# Adafruit_NeoPixel_8_Stick.net
KiCad netlist of a schematic drawn in EAGLE
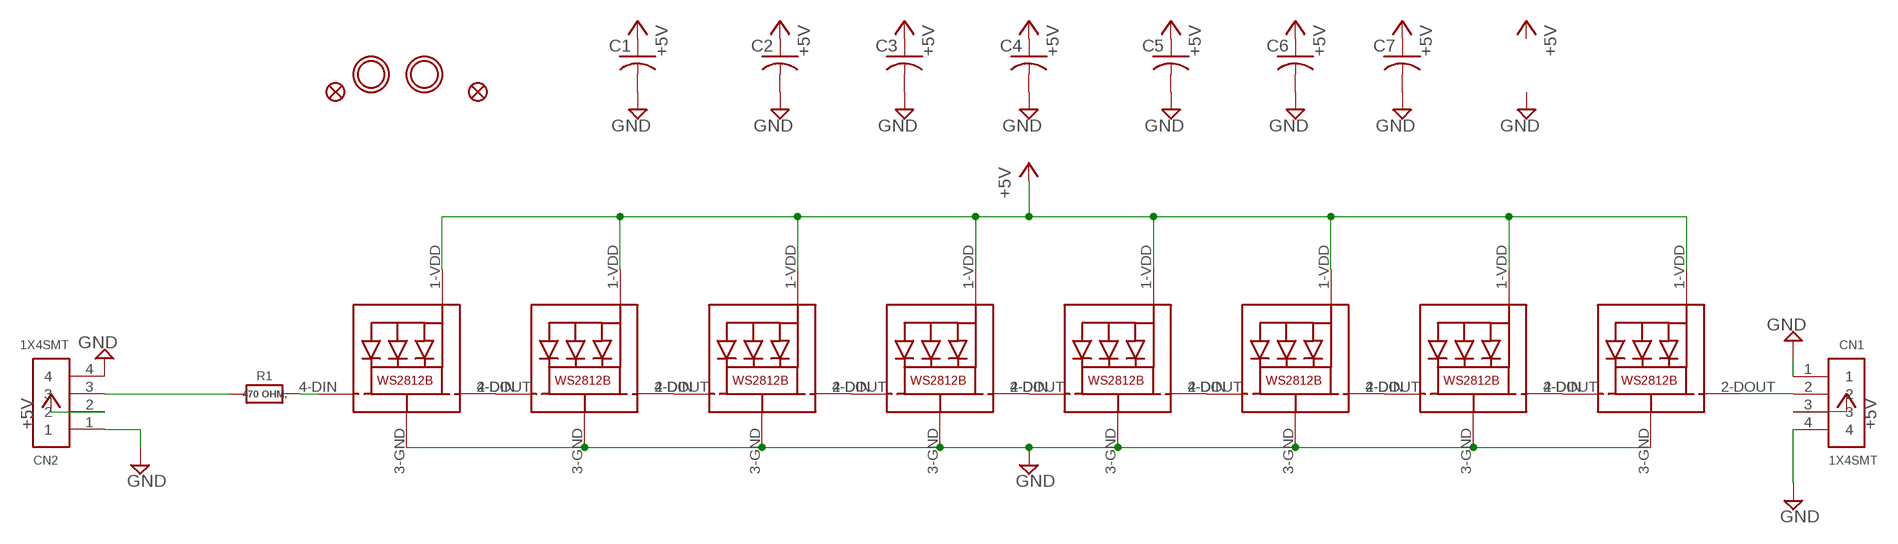
[diagram p0: schematic, sheet 1]

(export (version "E")
  (design (tool "Eeschema 10.0.6"))
  (components
    (comp (ref "C1")
      (value "C-USC0805K")
      (footprint "eagle-import:C0805K")
      (libsource (lib "eagle-import") (part "C-USC0805K"))
    )
    (comp (ref "C2")
      (value "C-USC0805K")
      (footprint "eagle-import:C0805K")
      (libsource (lib "eagle-import") (part "C-USC0805K"))
    )
    (comp (ref "C3")
      (value "C-USC0805K")
      (footprint "eagle-import:C0805K")
      (libsource (lib "eagle-import") (part "C-USC0805K"))
    )
    (comp (ref "C4")
      (value "C-USC0805K")
      (footprint "eagle-import:C0805K")
      (libsource (lib "eagle-import") (part "C-USC0805K"))
    )
    (comp (ref "C5")
      (value "C-USC0805K")
      (footprint "eagle-import:C0805K")
      (libsource (lib "eagle-import") (part "C-USC0805K"))
    )
    (comp (ref "C6")
      (value "C-USC0805K")
      (footprint "eagle-import:C0805K")
      (libsource (lib "eagle-import") (part "C-USC0805K"))
    )
    (comp (ref "C7")
      (value "C-USC0805K")
      (footprint "eagle-import:C0805K")
      (libsource (lib "eagle-import") (part "C-USC0805K"))
    )
    (comp (ref "CN1")
      (value "1X4SMT")
      (footprint "eagle-import:1X4-SMT")
      (libsource (lib "eagle-import") (part "1X4SMT"))
    )
    (comp (ref "CN2")
      (value "1X4SMT")
      (footprint "eagle-import:1X4-SMT")
      (libsource (lib "eagle-import") (part "1X4SMT"))
    )
    (comp (ref "FID1")
      (value "FIDUCIAL\"\"")
      (footprint "eagle-import:FIDUCIAL_1MM")
      (libsource (lib "eagle-import") (part "FIDUCIAL{dblquote}{dblquote}"))
    )
    (comp (ref "FID3")
      (value "FIDUCIAL\"\"")
      (footprint "eagle-import:FIDUCIAL_1MM")
      (libsource (lib "eagle-import") (part "FIDUCIAL{dblquote}{dblquote}"))
    )
    (comp (ref "LED1")
      (value "WS2812B5050")
      (footprint "eagle-import:WS2812B")
      (libsource (lib "eagle-import") (part "WS2812B5050"))
    )
    (comp (ref "LED2")
      (value "WS2812B5050")
      (footprint "eagle-import:WS2812B")
      (libsource (lib "eagle-import") (part "WS2812B5050"))
    )
    (comp (ref "LED3")
      (value "WS2812B5050")
      (footprint "eagle-import:WS2812B")
      (libsource (lib "eagle-import") (part "WS2812B5050"))
    )
    (comp (ref "LED4")
      (value "WS2812B5050")
      (footprint "eagle-import:WS2812B")
      (libsource (lib "eagle-import") (part "WS2812B5050"))
    )
    (comp (ref "LED5")
      (value "WS2812B5050")
      (footprint "eagle-import:WS2812B")
      (libsource (lib "eagle-import") (part "WS2812B5050"))
    )
    (comp (ref "LED6")
      (value "WS2812B5050")
      (footprint "eagle-import:WS2812B")
      (libsource (lib "eagle-import") (part "WS2812B5050"))
    )
    (comp (ref "LED7")
      (value "WS2812B5050")
      (footprint "eagle-import:WS2812B")
      (libsource (lib "eagle-import") (part "WS2812B5050"))
    )
    (comp (ref "LED8")
      (value "WS2812B5050")
      (footprint "eagle-import:WS2812B")
      (libsource (lib "eagle-import") (part "WS2812B5050"))
    )
    (comp (ref "R1")
      (value "470 OHM,")
      (footprint "eagle-import:_0805MP")
      (libsource (lib "eagle-import") (part "RESISTOR_0805MP"))
    )
    (comp (ref "U$2")
      (value "MOUNTINGHOLE2.0")
      (footprint "eagle-import:MOUNTINGHOLE_2.0_PLATED")
      (libsource (lib "eagle-import") (part "MOUNTINGHOLE2.0"))
    )
    (comp (ref "U$3")
      (value "MOUNTINGHOLE2.0")
      (footprint "eagle-import:MOUNTINGHOLE_2.0_PLATED")
      (libsource (lib "eagle-import") (part "MOUNTINGHOLE2.0"))
    )
  )
  (nets
    (net (code "1") (name "+5V") (class "Default")
      (node (ref "C1") (pin "1") (pinfunction "1_1") (pintype "passive"))
      (node (ref "C2") (pin "1") (pinfunction "1_1") (pintype "passive"))
      (node (ref "C3") (pin "1") (pinfunction "1_1") (pintype "passive"))
      (node (ref "C4") (pin "1") (pinfunction "1_1") (pintype "passive"))
      (node (ref "C5") (pin "1") (pinfunction "1_1") (pintype "passive"))
      (node (ref "C6") (pin "1") (pinfunction "1_1") (pintype "passive"))
      (node (ref "C7") (pin "1") (pinfunction "1_1") (pintype "passive"))
      (node (ref "CN1") (pin "3") (pinfunction "3_3") (pintype "bidirectional"))
      (node (ref "CN2") (pin "2") (pinfunction "2_2") (pintype "bidirectional"))
      (node (ref "LED1") (pin "1-VDD") (pinfunction "VDD_1-VDD") (pintype "power_in"))
      (node (ref "LED2") (pin "1-VDD") (pinfunction "VDD_1-VDD") (pintype "power_in"))
      (node (ref "LED3") (pin "1-VDD") (pinfunction "VDD_1-VDD") (pintype "power_in"))
      (node (ref "LED4") (pin "1-VDD") (pinfunction "VDD_1-VDD") (pintype "power_in"))
      (node (ref "LED5") (pin "1-VDD") (pinfunction "VDD_1-VDD") (pintype "power_in"))
      (node (ref "LED6") (pin "1-VDD") (pinfunction "VDD_1-VDD") (pintype "power_in"))
      (node (ref "LED7") (pin "1-VDD") (pinfunction "VDD_1-VDD") (pintype "power_in"))
      (node (ref "LED8") (pin "1-VDD") (pinfunction "VDD_1-VDD") (pintype "power_in"))
    )
    (net (code "2") (name "GND") (class "Default")
      (node (ref "C1") (pin "2") (pinfunction "2_2") (pintype "passive"))
      (node (ref "C2") (pin "2") (pinfunction "2_2") (pintype "passive"))
      (node (ref "C3") (pin "2") (pinfunction "2_2") (pintype "passive"))
      (node (ref "C4") (pin "2") (pinfunction "2_2") (pintype "passive"))
      (node (ref "C5") (pin "2") (pinfunction "2_2") (pintype "passive"))
      (node (ref "C6") (pin "2") (pinfunction "2_2") (pintype "passive"))
      (node (ref "C7") (pin "2") (pinfunction "2_2") (pintype "passive"))
      (node (ref "CN1") (pin "1") (pinfunction "1_1") (pintype "bidirectional"))
      (node (ref "CN1") (pin "4") (pinfunction "4_4") (pintype "bidirectional"))
      (node (ref "CN2") (pin "1") (pinfunction "1_1") (pintype "bidirectional"))
      (node (ref "CN2") (pin "4") (pinfunction "4_4") (pintype "bidirectional"))
      (node (ref "LED1") (pin "3-GND") (pinfunction "GND_3-GND") (pintype "power_in"))
      (node (ref "LED2") (pin "3-GND") (pinfunction "GND_3-GND") (pintype "power_in"))
      (node (ref "LED3") (pin "3-GND") (pinfunction "GND_3-GND") (pintype "power_in"))
      (node (ref "LED4") (pin "3-GND") (pinfunction "GND_3-GND") (pintype "power_in"))
      (node (ref "LED5") (pin "3-GND") (pinfunction "GND_3-GND") (pintype "power_in"))
      (node (ref "LED6") (pin "3-GND") (pinfunction "GND_3-GND") (pintype "power_in"))
      (node (ref "LED7") (pin "3-GND") (pinfunction "GND_3-GND") (pintype "power_in"))
      (node (ref "LED8") (pin "3-GND") (pinfunction "GND_3-GND") (pintype "power_in"))
    )
    (net (code "3") (name "Net-(CN2-Pad3)") (class "Default")
      (node (ref "CN2") (pin "3") (pinfunction "3_3") (pintype "bidirectional"))
      (node (ref "R1") (pin "1") (pinfunction "1_1") (pintype "passive"))
    )
    (net (code "4") (name "Net-(LED1-DI)") (class "Default")
      (node (ref "LED1") (pin "4-DIN") (pinfunction "DI_4-DIN") (pintype "input"))
      (node (ref "R1") (pin "2") (pinfunction "2_2") (pintype "passive"))
    )
    (net (code "5") (name "Net-(LED1-DO)") (class "Default")
      (node (ref "LED1") (pin "2-DOUT") (pinfunction "DO_2-DOUT") (pintype "output"))
      (node (ref "LED2") (pin "4-DIN") (pinfunction "DI_4-DIN") (pintype "input"))
    )
    (net (code "6") (name "Net-(LED2-DO)") (class "Default")
      (node (ref "LED2") (pin "2-DOUT") (pinfunction "DO_2-DOUT") (pintype "output"))
      (node (ref "LED3") (pin "4-DIN") (pinfunction "DI_4-DIN") (pintype "input"))
    )
    (net (code "7") (name "Net-(LED3-DO)") (class "Default")
      (node (ref "LED3") (pin "2-DOUT") (pinfunction "DO_2-DOUT") (pintype "output"))
      (node (ref "LED4") (pin "4-DIN") (pinfunction "DI_4-DIN") (pintype "input"))
    )
    (net (code "8") (name "Net-(LED4-DO)") (class "Default")
      (node (ref "LED4") (pin "2-DOUT") (pinfunction "DO_2-DOUT") (pintype "output"))
      (node (ref "LED5") (pin "4-DIN") (pinfunction "DI_4-DIN") (pintype "input"))
    )
    (net (code "9") (name "Net-(LED5-DO)") (class "Default")
      (node (ref "LED5") (pin "2-DOUT") (pinfunction "DO_2-DOUT") (pintype "output"))
      (node (ref "LED6") (pin "4-DIN") (pinfunction "DI_4-DIN") (pintype "input"))
    )
    (net (code "10") (name "Net-(LED6-DO)") (class "Default")
      (node (ref "LED6") (pin "2-DOUT") (pinfunction "DO_2-DOUT") (pintype "output"))
      (node (ref "LED7") (pin "4-DIN") (pinfunction "DI_4-DIN") (pintype "input"))
    )
    (net (code "11") (name "Net-(LED7-DO)") (class "Default")
      (node (ref "LED7") (pin "2-DOUT") (pinfunction "DO_2-DOUT") (pintype "output"))
      (node (ref "LED8") (pin "4-DIN") (pinfunction "DI_4-DIN") (pintype "input"))
    )
    (net (code "12") (name "Net-(LED8-DO)") (class "Default")
      (node (ref "CN1") (pin "2") (pinfunction "2_2") (pintype "bidirectional"))
      (node (ref "LED8") (pin "2-DOUT") (pinfunction "DO_2-DOUT") (pintype "output"))
    )
  )
)
